# 02_Connectors.net
KiCad netlist of a schematic drawn in Altium Designer
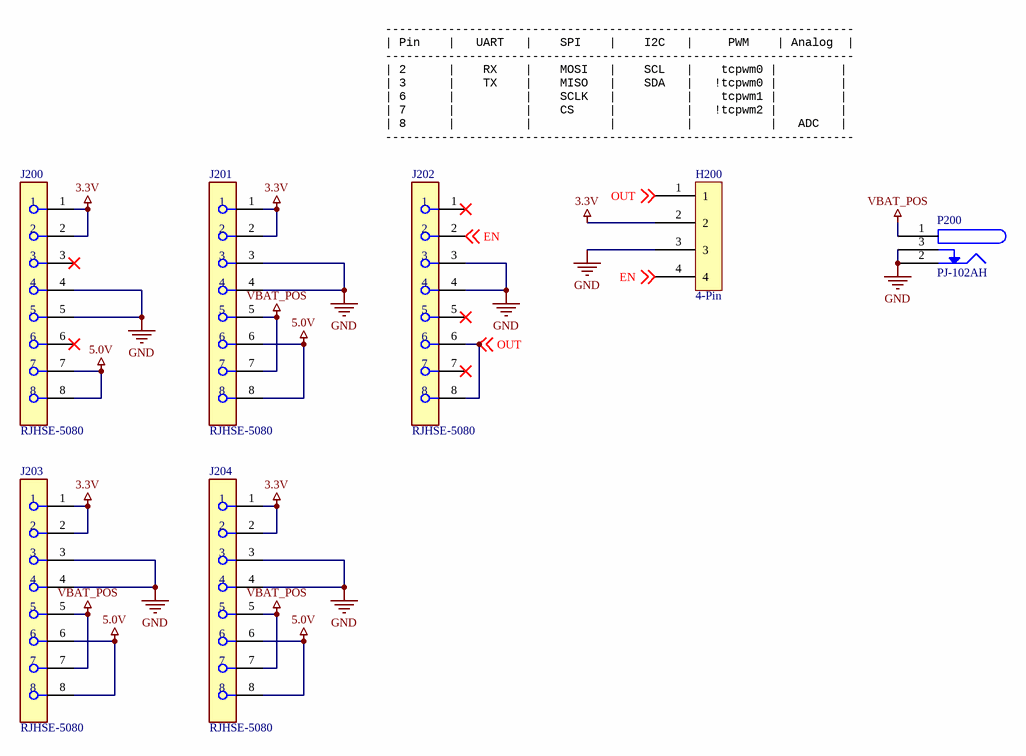
[diagram p0: 02_Connectors.SchDoc]

(export (version "E")
  (design (tool "Eeschema 10.0.6"))
  (components
    (comp (ref "H200")
      (value "4-Pin")
      (footprint "4X1HDR")
      (description "Conn Unshrouded Header HDR 4 POS 2.54mm Solder ST Thru-Hole Bag")
      (fields
        (field (name "MANUFACTURER") "Adam Equipment")
        (field (name "MANUFACTURER PART NUMBER") "PH1-04-UA")
      )
      (libsource (lib "ECE453") (part "4-Pin"))
    )
    (comp (ref "J200")
      (value "RJHSE-5080")
      (footprint "FP-RJHSE-5080-MFG")
      (description "CONN MOD JACK 8P8C R/A UNSHLD")
      (fields
        (field (name "OCTOPART") "https://octopart.com/rjhse-5080-amphenol-45060")
        (field (name "MANUFACTURER") "Amphenol")
      )
      (libsource (lib "Altium Content Vault") (part "b0a0b555dd3abf3683e7c330df25cc4"))
    )
    (comp (ref "J201")
      (value "RJHSE-5080")
      (footprint "FP-RJHSE-5080-MFG")
      (description "CONN MOD JACK 8P8C R/A UNSHLD")
      (fields
        (field (name "OCTOPART") "https://octopart.com/rjhse-5080-amphenol-45060")
        (field (name "MANUFACTURER") "Amphenol")
      )
      (libsource (lib "Altium Content Vault") (part "b0a0b555dd3abf3683e7c330df25cc4"))
    )
    (comp (ref "J202")
      (value "RJHSE-5080")
      (footprint "FP-RJHSE-5080-MFG")
      (description "CONN MOD JACK 8P8C R/A UNSHLD")
      (fields
        (field (name "OCTOPART") "https://octopart.com/rjhse-5080-amphenol-45060")
        (field (name "MANUFACTURER") "Amphenol")
      )
      (libsource (lib "Altium Content Vault") (part "b0a0b555dd3abf3683e7c330df25cc4"))
    )
    (comp (ref "J203")
      (value "RJHSE-5080")
      (footprint "FP-RJHSE-5080-MFG")
      (description "CONN MOD JACK 8P8C R/A UNSHLD")
      (fields
        (field (name "OCTOPART") "https://octopart.com/rjhse-5080-amphenol-45060")
        (field (name "MANUFACTURER") "Amphenol")
      )
      (libsource (lib "Altium Content Vault") (part "b0a0b555dd3abf3683e7c330df25cc4"))
    )
    (comp (ref "J204")
      (value "RJHSE-5080")
      (footprint "FP-RJHSE-5080-MFG")
      (description "CONN MOD JACK 8P8C R/A UNSHLD")
      (fields
        (field (name "OCTOPART") "https://octopart.com/rjhse-5080-amphenol-45060")
        (field (name "MANUFACTURER") "Amphenol")
      )
      (libsource (lib "Altium Content Vault") (part "b0a0b555dd3abf3683e7c330df25cc4"))
    )
    (comp (ref "P200")
      (value "PJ-102")
      (footprint "PJ-102")
      (description "CONN PWR JACK 2.1X5.5MM HIGH CUR")
      (fields (field (name "MANUFACTURER") "CUI Inc") (field (name "MANUFACTURER PART NUMBER") "PJ-102AH"))
      (libsource (lib "ECE453") (part "CONN JACK PWR W/SW"))
    )
  )
  (nets
    (net (code "1") (name "3.3V") (class "Default")
      (node (ref "H200") (pin "2") (pinfunction "2_2") (pintype "passive"))
      (node (ref "J200") (pin "1") (pinfunction "1_1") (pintype "passive"))
      (node (ref "J200") (pin "2") (pinfunction "2_2") (pintype "passive"))
      (node (ref "J201") (pin "1") (pinfunction "1_1") (pintype "passive"))
      (node (ref "J201") (pin "2") (pinfunction "2_2") (pintype "passive"))
      (node (ref "J203") (pin "1") (pinfunction "1_1") (pintype "passive"))
      (node (ref "J203") (pin "2") (pinfunction "2_2") (pintype "passive"))
      (node (ref "J204") (pin "1") (pinfunction "1_1") (pintype "passive"))
      (node (ref "J204") (pin "2") (pinfunction "2_2") (pintype "passive"))
    )
    (net (code "2") (name "5.0V") (class "Default")
      (node (ref "J200") (pin "7") (pinfunction "7_7") (pintype "passive"))
      (node (ref "J200") (pin "8") (pinfunction "8_8") (pintype "passive"))
      (node (ref "J201") (pin "6") (pinfunction "6_6") (pintype "passive"))
      (node (ref "J201") (pin "8") (pinfunction "8_8") (pintype "passive"))
      (node (ref "J203") (pin "6") (pinfunction "6_6") (pintype "passive"))
      (node (ref "J203") (pin "8") (pinfunction "8_8") (pintype "passive"))
      (node (ref "J204") (pin "6") (pinfunction "6_6") (pintype "passive"))
      (node (ref "J204") (pin "8") (pinfunction "8_8") (pintype "passive"))
    )
    (net (code "3") (name "EN") (class "Default")
      (node (ref "H200") (pin "4") (pinfunction "4_4") (pintype "passive"))
      (node (ref "J202") (pin "2") (pinfunction "2_2") (pintype "passive"))
    )
    (net (code "4") (name "GND") (class "Default")
      (node (ref "H200") (pin "3") (pinfunction "3_3") (pintype "passive"))
      (node (ref "J200") (pin "4") (pinfunction "4_4") (pintype "passive"))
      (node (ref "J200") (pin "5") (pinfunction "5_5") (pintype "passive"))
      (node (ref "J201") (pin "3") (pinfunction "3_3") (pintype "passive"))
      (node (ref "J201") (pin "4") (pinfunction "4_4") (pintype "passive"))
      (node (ref "J202") (pin "3") (pinfunction "3_3") (pintype "passive"))
      (node (ref "J202") (pin "4") (pinfunction "4_4") (pintype "passive"))
      (node (ref "J203") (pin "3") (pinfunction "3_3") (pintype "passive"))
      (node (ref "J203") (pin "4") (pinfunction "4_4") (pintype "passive"))
      (node (ref "J204") (pin "3") (pinfunction "3_3") (pintype "passive"))
      (node (ref "J204") (pin "4") (pinfunction "4_4") (pintype "passive"))
      (node (ref "P200") (pin "2") (pinfunction "2_2") (pintype "passive"))
      (node (ref "P200") (pin "3") (pinfunction "3_3") (pintype "passive"))
    )
    (net (code "5") (name "OUT") (class "Default")
      (node (ref "H200") (pin "1") (pinfunction "1_1") (pintype "passive"))
      (node (ref "J202") (pin "6") (pinfunction "6_6") (pintype "passive"))
      (node (ref "J202") (pin "8") (pinfunction "8_8") (pintype "passive"))
    )
    (net (code "6") (name "VBAT_POS") (class "Default")
      (node (ref "J201") (pin "5") (pinfunction "5_5") (pintype "passive"))
      (node (ref "J201") (pin "7") (pinfunction "7_7") (pintype "passive"))
      (node (ref "J203") (pin "5") (pinfunction "5_5") (pintype "passive"))
      (node (ref "J203") (pin "7") (pinfunction "7_7") (pintype "passive"))
      (node (ref "J204") (pin "5") (pinfunction "5_5") (pintype "passive"))
      (node (ref "J204") (pin "7") (pinfunction "7_7") (pintype "passive"))
      (node (ref "P200") (pin "1") (pinfunction "1_1") (pintype "passive"))
    )
    (net (code "7") (name "unconnected-(J200-Pad3)") (class "Default")
      (node (ref "J200") (pin "3") (pinfunction "3_3") (pintype "passive+no_connect"))
    )
    (net (code "8") (name "unconnected-(J200-Pad6)") (class "Default")
      (node (ref "J200") (pin "6") (pinfunction "6_6") (pintype "passive+no_connect"))
    )
    (net (code "9") (name "unconnected-(J202-Pad1)") (class "Default")
      (node (ref "J202") (pin "1") (pinfunction "1_1") (pintype "passive+no_connect"))
    )
    (net (code "10") (name "unconnected-(J202-Pad5)") (class "Default")
      (node (ref "J202") (pin "5") (pinfunction "5_5") (pintype "passive+no_connect"))
    )
    (net (code "11") (name "unconnected-(J202-Pad7)") (class "Default")
      (node (ref "J202") (pin "7") (pinfunction "7_7") (pintype "passive+no_connect"))
    )
  )
)
